# PWRsupply.net
KiCad netlist of a schematic drawn in Altium Designer
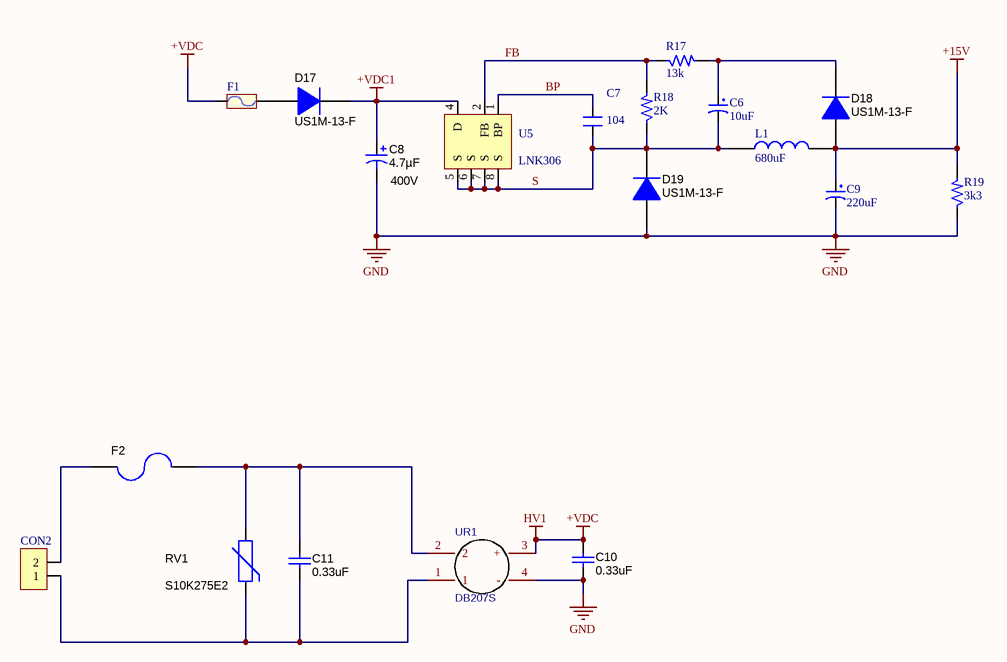
[diagram p0: PWRsupply.SchDoc]

(export (version "E")
  (design (tool "Eeschema 10.0.6"))
  (components
    (comp (ref "C6")
      (value "10uF")
      (footprint "TU_NHOM_10uF_MH")
      (description "TU_NHOM_10uF_25V_MH")
      (libsource (lib "MH_DA_THU_VIEN_16122016") (part "TU_NHOM_10uF_25V_MH"))
    )
    (comp (ref "C7")
      (value "104")
      (footprint "0805_Cap")
      (description "Cap SMD")
      (libsource (lib "hatcatbietbay") (part "CM"))
    )
    (comp (ref "C8")
      (value "400AX6R8M8x11")
      (footprint "CAP-PANACAP-G-GENERIC")
      (description "CAP, AL, 6.8uF, 400V, +/-20%, TH")
      (fields
        (field (name "VALUEDISPLAYED") "4.7µF")
        (field (name "MANUFACTURER") "Rubycon")
        (field (name "VALUE2") "400V")
        (field (name "PUBLISHER") "Texas Instruments")
      )
      (libsource (lib "Capacitor_Aluminum") (part "400AX6R8M8x11"))
    )
    (comp (ref "C9")
      (value "220uF")
      (footprint "TU_NHOM_2.5_MH")
      (description "TU_NHOM_220uF_25V_MH")
      (libsource (lib "MH_DA_THU_VIEN_16122016") (part "TU_NHOM_220uF_25V_MH"))
    )
    (comp (ref "C10")
      (value "0.33uF")
      (footprint "B32922_12mm")
      (description "CAP FILM 0.33UF 630VDC RADIAL")
      (fields
        (field (name "PARTNUMBER") "B32922C3334M189")
        (field (name "MANUFACTURER") "EPCOS(TDK)")
        (field (name "SYMBOLCREATOR") "x0199378")
      )
      (libsource (lib "All-Final Symbols") (part "BFC233620154"))
    )
    (comp (ref "C11")
      (value "0.33uF")
      (footprint "B32922_12mm")
      (description "CAP FILM 0.33UF 630VDC RADIAL")
      (fields
        (field (name "PARTNUMBER") "B32922C3334M189")
        (field (name "MANUFACTURER") "EPCOS(TDK)")
        (field (name "SYMBOLCREATOR") "x0199378")
      )
      (libsource (lib "All-Final Symbols") (part "BFC233620154"))
    )
    (comp (ref "CON2")
      (value "CON 2 EDG 5.08_MH")
      (footprint "CON 2 EDG 5.08")
      (description "CON 2 EDG 5.08 (xanh cong)")
      (libsource (lib "mySch") (part "CON 2 EDG 5.08_MH"))
    )
    (comp (ref "D17")
      (value "US1M-13-F")
      (footprint "SMB")
      (description "Diode, Ultrafast, 600V, 1A, SMB")
      (fields
        (field (name "PARTNUMBER") "US1M-13-F")
        (field (name "MANUFACTURER") "Diodes Inc.")
        (field (name "PUBLISHER") "Texas Instruments")
      )
      (libsource (lib "Diode") (part "MURS160-13-F"))
    )
    (comp (ref "D18")
      (value "US1M-13-F")
      (footprint "SMB")
      (description "Diode, Ultrafast, 600V, 1A, SMB")
      (fields
        (field (name "PARTNUMBER") "US1M-13-F")
        (field (name "MANUFACTURER") "Diodes Inc.")
        (field (name "PUBLISHER") "Texas Instruments")
      )
      (libsource (lib "Diode") (part "MURS160-13-F"))
    )
    (comp (ref "D19")
      (value "US1M-13-F")
      (footprint "SMB")
      (description "Diode, Ultrafast, 600V, 1A, SMB")
      (fields
        (field (name "PARTNUMBER") "US1M-13-F")
        (field (name "MANUFACTURER") "Diodes Inc.")
        (field (name "PUBLISHER") "Texas Instruments")
      )
      (libsource (lib "Diode") (part "MURS160-13-F"))
    )
    (comp (ref "F1")
      (value "FUSE_AUTO_0.5A 8V 1206_MH")
      (footprint "FUSE 1206")
      (description "Fuse")
      (libsource (lib "MH_DA_THU_VIEN_16122016") (part "FUSE_AUTO_0.5A 8V 1206_MH"))
    )
    (comp (ref "F2")
      (value "37015000430")
      (footprint "Fuse 5x20")
      (description "FUSE BOARD MOUNT 5A 250VAC RAD")
      (fields (field (name "MANUFACTURER") "Littelfuse Inc") (field (name "PUBLISHER") "Texas Instruments"))
      (libsource (lib "Fuse") (part "0216008.MXESPP"))
    )
    (comp (ref "L1")
      (value "680uF")
      (footprint "Inductor 4.5x5")
      (libsource (lib "MH_DA_THU_VIEN_16122016") (part "Inductor 4.5x5_MH"))
    )
    (comp (ref "R17")
      (value "13k")
      (footprint "0805_R")
      (description "Resistor 1/4W")
      (libsource (lib "hatcatbietbay") (part "R"))
    )
    (comp (ref "R18")
      (value "2K")
      (footprint "0805_R")
      (description "Resistor 1/4W")
      (libsource (lib "hatcatbietbay") (part "R"))
    )
    (comp (ref "R19")
      (value "3k3")
      (footprint "0805_R")
      (description "Resistor 1/4W")
      (libsource (lib "hatcatbietbay") (part "R"))
    )
    (comp (ref "RV1")
      (value "S10K275E2")
      (footprint "VAR_S10K275E2")
      (description "Varistor 275V RMS 10MM Radial, TH")
      (fields
        (field (name "MANUFACTURER") "EPCOS Inc")
        (field (name "SYMBOLCREATOR") "a0412235")
        (field (name "PUBLISHER") "Texas Instruments")
      )
      (libsource (lib "Other_Passive") (part "S10K275E2"))
    )
    (comp (ref "U5") (value "LNK306") (footprint "SOP 7") (libsource (lib "LNK304") (part "Component_1")))
    (comp (ref "UR1")
      (value "DB207S")
      (footprint "DB207S")
      (fields (field (name "BOM_SUPPLIER PART") "C84160"))
      (libsource (lib "mySch") (part "DB207S"))
    )
  )
  (nets
    (net (code "1") (name "+15V") (class "Default")
      (node (ref "C9") (pin "1") (pinfunction "1_1") (pintype "passive"))
      (node (ref "D18") (pin "2") (pinfunction "A_2") (pintype "passive"))
      (node (ref "L1") (pin "2") (pinfunction "2_2") (pintype "passive"))
      (node (ref "R19") (pin "2") (pinfunction "2_2") (pintype "passive"))
    )
    (net (code "2") (name "+VDC") (class "Default")
      (node (ref "C10") (pin "2") (pinfunction "2_2") (pintype "passive"))
      (node (ref "F1") (pin "1") (pinfunction "1_1") (pintype "passive"))
      (node (ref "UR1") (pin "3") (pinfunction "+_3") (pintype "passive"))
    )
    (net (code "3") (name "+VDC1") (class "Default")
      (node (ref "C8") (pin "1") (pinfunction "+_1") (pintype "passive"))
      (node (ref "D17") (pin "1") (pinfunction "K_1") (pintype "passive"))
      (node (ref "U5") (pin "4") (pinfunction "D_4") (pintype "passive"))
    )
    (net (code "4") (name "/BP") (class "Default")
      (node (ref "C7") (pin "2") (pinfunction "2_2") (pintype "passive"))
      (node (ref "U5") (pin "1") (pinfunction "BP_1") (pintype "passive"))
    )
    (net (code "5") (name "/FB") (class "Default")
      (node (ref "R17") (pin "1") (pinfunction "1_1") (pintype "passive"))
      (node (ref "R18") (pin "2") (pinfunction "2_2") (pintype "passive"))
      (node (ref "U5") (pin "2") (pinfunction "FB_2") (pintype "passive"))
    )
    (net (code "6") (name "/S") (class "Default")
      (node (ref "C6") (pin "2") (pinfunction "2_2") (pintype "passive"))
      (node (ref "C7") (pin "1") (pinfunction "1_1") (pintype "passive"))
      (node (ref "D19") (pin "1") (pinfunction "K_1") (pintype "passive"))
      (node (ref "L1") (pin "1") (pinfunction "1_1") (pintype "passive"))
      (node (ref "R18") (pin "1") (pinfunction "1_1") (pintype "passive"))
      (node (ref "U5") (pin "5") (pinfunction "S_5") (pintype "passive"))
      (node (ref "U5") (pin "6") (pinfunction "S_6") (pintype "passive"))
      (node (ref "U5") (pin "7") (pinfunction "S_7") (pintype "passive"))
      (node (ref "U5") (pin "8") (pinfunction "S_8") (pintype "passive"))
    )
    (net (code "7") (name "GND") (class "Default")
      (node (ref "C10") (pin "1") (pinfunction "1_1") (pintype "passive"))
      (node (ref "C8") (pin "2") (pinfunction "-_2") (pintype "passive"))
      (node (ref "C9") (pin "2") (pinfunction "2_2") (pintype "passive"))
      (node (ref "D19") (pin "2") (pinfunction "A_2") (pintype "passive"))
      (node (ref "R19") (pin "1") (pinfunction "1_1") (pintype "passive"))
      (node (ref "UR1") (pin "4") (pinfunction "-_4") (pintype "passive"))
    )
    (net (code "8") (name "Net-(C11-Pad1)") (class "Default")
      (node (ref "C11") (pin "1") (pinfunction "1_1") (pintype "passive"))
      (node (ref "CON2") (pin "1") (pinfunction "1_1") (pintype "passive"))
      (node (ref "RV1") (pin "2") (pinfunction "2_2") (pintype "passive"))
      (node (ref "UR1") (pin "1") (pinfunction "1_1") (pintype "passive"))
    )
    (net (code "9") (name "Net-(C11-Pad2)") (class "Default")
      (node (ref "C11") (pin "2") (pinfunction "2_2") (pintype "passive"))
      (node (ref "F2") (pin "1") (pinfunction "1_1") (pintype "passive"))
      (node (ref "RV1") (pin "1") (pinfunction "1_1") (pintype "passive"))
      (node (ref "UR1") (pin "2") (pinfunction "2_2") (pintype "passive"))
    )
    (net (code "10") (name "Net-(CON2-Pad2)") (class "Default")
      (node (ref "CON2") (pin "2") (pinfunction "2_2") (pintype "passive"))
      (node (ref "F2") (pin "2") (pinfunction "2_2") (pintype "passive"))
    )
    (net (code "11") (name "Net-(D17-A)") (class "Default")
      (node (ref "D17") (pin "2") (pinfunction "A_2") (pintype "passive"))
      (node (ref "F1") (pin "2") (pinfunction "2_2") (pintype "passive"))
    )
    (net (code "12") (name "Net-(D18-K)") (class "Default")
      (node (ref "C6") (pin "1") (pinfunction "1_1") (pintype "passive"))
      (node (ref "D18") (pin "1") (pinfunction "K_1") (pintype "passive"))
      (node (ref "R17") (pin "2") (pinfunction "2_2") (pintype "passive"))
    )
  )
)
